# pll_schematic.net
KiCad netlist of a schematic drawn in Altium Designer
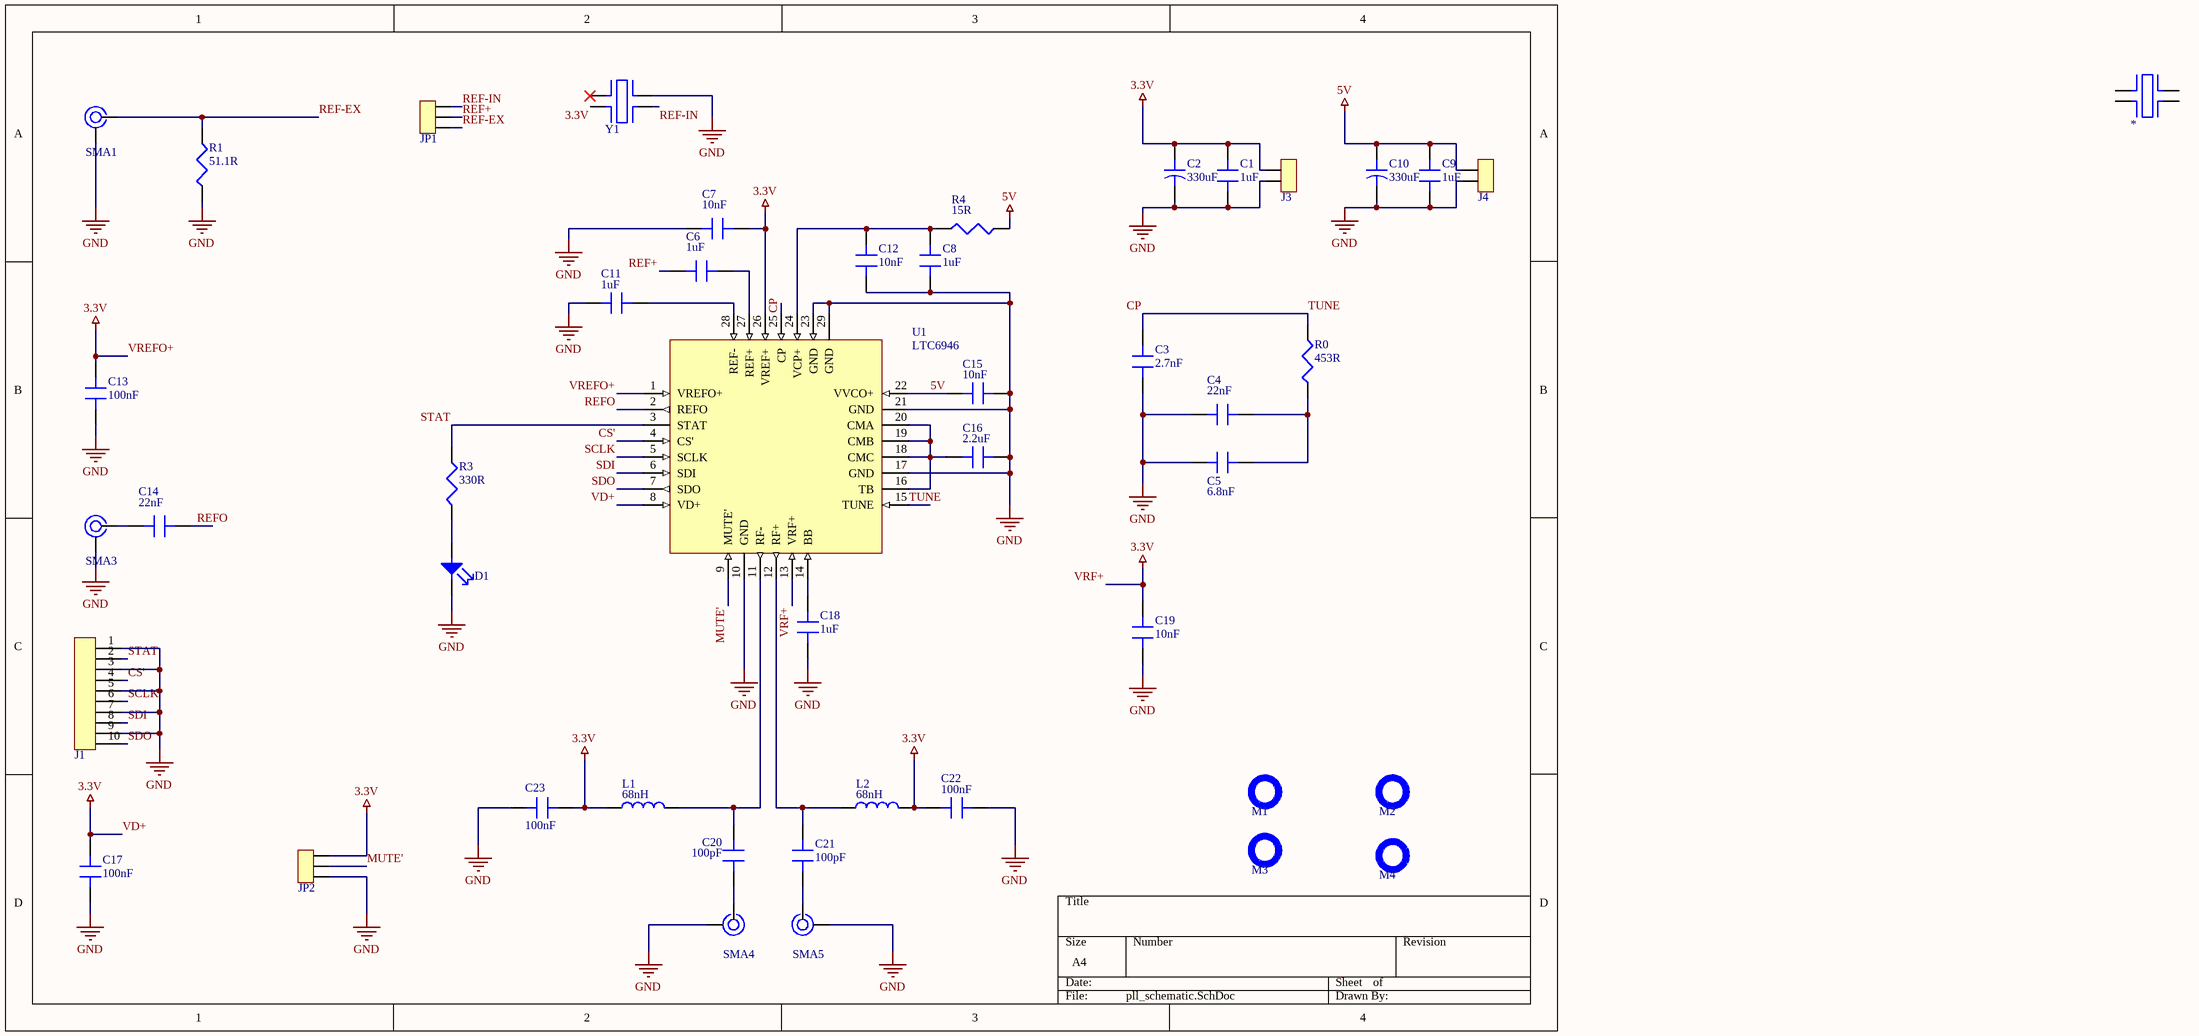
[diagram p0: pll_schematic.SchDoc]

(export (version "E")
  (design (tool "Eeschema 10.0.6"))
  (components
    (comp (ref "*") (value "-") (libsource (lib "pll_schematic_lib") (part "OSC")))
    (comp (ref "C1") (value "1uF") (footprint "C0603") (libsource (lib "pll_schematic_lib") (part "C")))
    (comp (ref "C2") (value "330uF") (footprint "C_TANT_D") (libsource (lib "pll_schematic_lib") (part "CP")))
    (comp (ref "C3") (value "2.7nF") (footprint "C0603") (libsource (lib "pll_schematic_lib") (part "C")))
    (comp (ref "C4") (value "22nF") (footprint "C0603") (libsource (lib "pll_schematic_lib") (part "C")))
    (comp (ref "C5") (value "6.8nF") (footprint "C0603") (libsource (lib "pll_schematic_lib") (part "C")))
    (comp (ref "C6") (value "1uF") (footprint "C0603") (libsource (lib "pll_schematic_lib") (part "C")))
    (comp (ref "C7") (value "10nF") (footprint "C0603") (libsource (lib "pll_schematic_lib") (part "C")))
    (comp (ref "C8") (value "1uF") (footprint "C0603") (libsource (lib "pll_schematic_lib") (part "C")))
    (comp (ref "C9") (value "1uF") (footprint "C0603") (libsource (lib "pll_schematic_lib") (part "C")))
    (comp (ref "C10")
      (value "330uF")
      (footprint "C_TANT_D")
      (libsource (lib "pll_schematic_lib") (part "CP"))
    )
    (comp (ref "C11") (value "1uF") (footprint "C0603") (libsource (lib "pll_schematic_lib") (part "C")))
    (comp (ref "C12") (value "10nF") (footprint "C0603") (libsource (lib "pll_schematic_lib") (part "C")))
    (comp (ref "C13") (value "100nF") (footprint "C0603") (libsource (lib "pll_schematic_lib") (part "C")))
    (comp (ref "C14") (value "22nF") (footprint "C0603") (libsource (lib "pll_schematic_lib") (part "C")))
    (comp (ref "C15") (value "10nF") (footprint "C0603") (libsource (lib "pll_schematic_lib") (part "C")))
    (comp (ref "C16") (value "2.2uF") (footprint "C0805") (libsource (lib "pll_schematic_lib") (part "C")))
    (comp (ref "C17") (value "100nF") (footprint "C0603") (libsource (lib "pll_schematic_lib") (part "C")))
    (comp (ref "C18") (value "1uF") (footprint "C0603") (libsource (lib "pll_schematic_lib") (part "C")))
    (comp (ref "C19") (value "10nF") (footprint "C0603") (libsource (lib "pll_schematic_lib") (part "C")))
    (comp (ref "C20") (value "100pF") (footprint "C0603") (libsource (lib "pll_schematic_lib") (part "C")))
    (comp (ref "C21") (value "100pF") (footprint "C0603") (libsource (lib "pll_schematic_lib") (part "C")))
    (comp (ref "C22") (value "100nF") (footprint "C0603") (libsource (lib "pll_schematic_lib") (part "C")))
    (comp (ref "C23") (value "100nF") (footprint "C0603") (libsource (lib "pll_schematic_lib") (part "C")))
    (comp (ref "D1") (value "-") (footprint "D0805") (libsource (lib "pll_schematic_lib") (part "LED")))
    (comp (ref "J1")
      (value "-")
      (footprint "IDC-2x05")
      (libsource (lib "pll_schematic_lib") (part "Conn_Gene_1x10"))
    )
    (comp (ref "J3")
      (value "-")
      (footprint "DG130-5.0")
      (libsource (lib "pll_schematic_lib") (part "Conn_Gene_1x02"))
    )
    (comp (ref "J4")
      (value "-")
      (footprint "DG130-5.0")
      (libsource (lib "pll_schematic_lib") (part "Conn_Gene_1x02"))
    )
    (comp (ref "JP1")
      (value "-")
      (footprint "PIN_HEADER_1x03")
      (libsource (lib "pll_schematic_lib") (part "Pin Header 1x03"))
    )
    (comp (ref "JP2")
      (value "-")
      (footprint "PIN_HEADER_1x03")
      (libsource (lib "pll_schematic_lib") (part "Pin Header 1x03"))
    )
    (comp (ref "L1") (value "68nH") (footprint "L0402") (libsource (lib "pll_schematic_lib") (part "L")))
    (comp (ref "L2") (value "68nH") (footprint "L0402") (libsource (lib "pll_schematic_lib") (part "L")))
    (comp (ref "M1")
      (value "MOUNTING_HOLE")
      (footprint "MOUNTING_HOLE_NP_M3")
      (description "Non-Plated")
      (libsource (lib "pll_schematic_lib") (part "MOUNTING_HOLE"))
    )
    (comp (ref "M2")
      (value "MOUNTING_HOLE")
      (footprint "MOUNTING_HOLE_NP_M3")
      (description "Non-Plated")
      (libsource (lib "pll_schematic_lib") (part "MOUNTING_HOLE"))
    )
    (comp (ref "M3")
      (value "MOUNTING_HOLE")
      (footprint "MOUNTING_HOLE_NP_M3")
      (description "Non-Plated")
      (libsource (lib "pll_schematic_lib") (part "MOUNTING_HOLE"))
    )
    (comp (ref "M4")
      (value "MOUNTING_HOLE")
      (footprint "MOUNTING_HOLE_NP_M3")
      (description "Non-Plated")
      (libsource (lib "pll_schematic_lib") (part "MOUNTING_HOLE"))
    )
    (comp (ref "R0") (value "453R") (footprint "R0603") (libsource (lib "pll_schematic_lib") (part "R")))
    (comp (ref "R1") (value "51.1R") (footprint "R0603") (libsource (lib "pll_schematic_lib") (part "R")))
    (comp (ref "R3") (value "330R") (footprint "R0603") (libsource (lib "pll_schematic_lib") (part "R")))
    (comp (ref "R4") (value "15R") (footprint "R0603") (libsource (lib "pll_schematic_lib") (part "R")))
    (comp (ref "SMA1") (value "-") (footprint "SMA") (libsource (lib "pll_schematic_lib") (part "SMA")))
    (comp (ref "SMA3") (value "-") (footprint "SMA") (libsource (lib "pll_schematic_lib") (part "SMA")))
    (comp (ref "SMA4") (value "-") (footprint "SMA") (libsource (lib "") (part "SMA_1")))
    (comp (ref "SMA5") (value "-") (footprint "SMA") (libsource (lib "pll_schematic_lib") (part "SMA")))
    (comp (ref "U1")
      (value "LTC6946")
      (footprint "QFN50P400X500X80_HS-29N_2")
      (libsource (lib "pll_schematic_lib") (part "LTC6946IUFD-1#PBF-ND"))
    )
    (comp (ref "Y1") (value "-") (footprint "XOSC") (libsource (lib "pll_schematic_lib") (part "OSC")))
  )
  (nets
    (net (code "1") (name "/CP") (class "Default")
      (node (ref "C3") (pin "2") (pinfunction "-_2") (pintype "passive"))
      (node (ref "R0") (pin "2") (pinfunction "-_2") (pintype "passive"))
      (node (ref "U1") (pin "15") (pinfunction "TUNE_15") (pintype "input"))
      (node (ref "U1") (pin "25") (pinfunction "CP_25") (pintype "input"))
    )
    (net (code "2") (name "/CS'") (class "Default")
      (node (ref "J1") (pin "4") (pinfunction "*_4") (pintype "passive"))
      (node (ref "U1") (pin "4") (pinfunction "CS'_4") (pintype "input"))
    )
    (net (code "3") (name "/MUTE'") (class "Default")
      (node (ref "JP2") (pin "2") (pinfunction "-_2") (pintype "passive"))
      (node (ref "U1") (pin "9") (pinfunction "MUTE'_9") (pintype "input"))
    )
    (net (code "4") (name "/REF+") (class "Default")
      (node (ref "C6") (pin "1") (pinfunction "-_1") (pintype "passive"))
      (node (ref "JP1") (pin "2") (pinfunction "-_2") (pintype "passive"))
    )
    (net (code "5") (name "/REF-EX") (class "Default")
      (node (ref "JP1") (pin "3") (pinfunction "-_3") (pintype "passive"))
      (node (ref "R1") (pin "2") (pinfunction "-_2") (pintype "passive"))
      (node (ref "SMA1") (pin "1") (pinfunction "-_1") (pintype "passive"))
    )
    (net (code "6") (name "/REF-IN") (class "Default")
      (node (ref "JP1") (pin "1") (pinfunction "-_1") (pintype "passive"))
      (node (ref "Y1") (pin "5") (pinfunction "5_5") (pintype "passive"))
    )
    (net (code "7") (name "/REFO") (class "Default")
      (node (ref "C14") (pin "2") (pinfunction "-_2") (pintype "passive"))
      (node (ref "U1") (pin "2") (pinfunction "REFO_2") (pintype "output"))
    )
    (net (code "8") (name "/SCLK") (class "Default")
      (node (ref "J1") (pin "6") (pinfunction "*_6") (pintype "passive"))
      (node (ref "U1") (pin "5") (pinfunction "SCLK_5") (pintype "input"))
    )
    (net (code "9") (name "/SDI") (class "Default")
      (node (ref "J1") (pin "8") (pinfunction "*_8") (pintype "passive"))
      (node (ref "U1") (pin "6") (pinfunction "SDI_6") (pintype "input"))
    )
    (net (code "10") (name "/SDO") (class "Default")
      (node (ref "J1") (pin "10") (pinfunction "*_10") (pintype "passive"))
      (node (ref "U1") (pin "7") (pinfunction "SDO_7") (pintype "output"))
    )
    (net (code "11") (name "/STAT") (class "Default")
      (node (ref "J1") (pin "2") (pinfunction "*_2") (pintype "passive"))
      (node (ref "R3") (pin "2") (pinfunction "-_2") (pintype "passive"))
      (node (ref "U1") (pin "3") (pinfunction "STAT_3") (pintype "passive"))
    )
    (net (code "12") (name "3.3V") (class "Default")
      (node (ref "C1") (pin "2") (pinfunction "-_2") (pintype "passive"))
      (node (ref "C13") (pin "2") (pinfunction "-_2") (pintype "passive"))
      (node (ref "C17") (pin "2") (pinfunction "-_2") (pintype "passive"))
      (node (ref "C19") (pin "2") (pinfunction "-_2") (pintype "passive"))
      (node (ref "C2") (pin "1") (pinfunction "-_1") (pintype "passive"))
      (node (ref "C22") (pin "1") (pinfunction "-_1") (pintype "passive"))
      (node (ref "C23") (pin "1") (pinfunction "-_1") (pintype "passive"))
      (node (ref "C7") (pin "1") (pinfunction "-_1") (pintype "passive"))
      (node (ref "J3") (pin "1") (pinfunction "-_1") (pintype "passive"))
      (node (ref "JP2") (pin "1") (pinfunction "-_1") (pintype "passive"))
      (node (ref "L1") (pin "1") (pinfunction "-_1") (pintype "passive"))
      (node (ref "L2") (pin "2") (pinfunction "-_2") (pintype "passive"))
      (node (ref "U1") (pin "1") (pinfunction "VREFO+_1") (pintype "input"))
      (node (ref "U1") (pin "13") (pinfunction "VRF+_13") (pintype "input"))
      (node (ref "U1") (pin "26") (pinfunction "VREF+_26") (pintype "input"))
      (node (ref "U1") (pin "8") (pinfunction "VD+_8") (pintype "input"))
      (node (ref "Y1") (pin "8") (pinfunction "8_8") (pintype "passive"))
    )
    (net (code "13") (name "5V") (class "Default")
      (node (ref "C10") (pin "1") (pinfunction "-_1") (pintype "passive"))
      (node (ref "C15") (pin "1") (pinfunction "-_1") (pintype "passive"))
      (node (ref "C9") (pin "1") (pinfunction "-_1") (pintype "passive"))
      (node (ref "J4") (pin "1") (pinfunction "-_1") (pintype "passive"))
      (node (ref "R4") (pin "2") (pinfunction "-_2") (pintype "passive"))
      (node (ref "U1") (pin "22") (pinfunction "VVCO+_22") (pintype "input"))
    )
    (net (code "14") (name "GND") (class "Default")
      (node (ref "C1") (pin "1") (pinfunction "-_1") (pintype "passive"))
      (node (ref "C10") (pin "2") (pinfunction "-_2") (pintype "passive"))
      (node (ref "C11") (pin "1") (pinfunction "-_1") (pintype "passive"))
      (node (ref "C12") (pin "2") (pinfunction "-_2") (pintype "passive"))
      (node (ref "C13") (pin "1") (pinfunction "-_1") (pintype "passive"))
      (node (ref "C15") (pin "2") (pinfunction "-_2") (pintype "passive"))
      (node (ref "C16") (pin "2") (pinfunction "-_2") (pintype "passive"))
      (node (ref "C17") (pin "1") (pinfunction "-_1") (pintype "passive"))
      (node (ref "C18") (pin "1") (pinfunction "-_1") (pintype "passive"))
      (node (ref "C19") (pin "1") (pinfunction "-_1") (pintype "passive"))
      (node (ref "C2") (pin "2") (pinfunction "-_2") (pintype "passive"))
      (node (ref "C22") (pin "2") (pinfunction "-_2") (pintype "passive"))
      (node (ref "C23") (pin "2") (pinfunction "-_2") (pintype "passive"))
      (node (ref "C3") (pin "1") (pinfunction "-_1") (pintype "passive"))
      (node (ref "C4") (pin "2") (pinfunction "-_2") (pintype "passive"))
      (node (ref "C5") (pin "2") (pinfunction "-_2") (pintype "passive"))
      (node (ref "C7") (pin "2") (pinfunction "-_2") (pintype "passive"))
      (node (ref "C8") (pin "1") (pinfunction "-_1") (pintype "passive"))
      (node (ref "C9") (pin "2") (pinfunction "-_2") (pintype "passive"))
      (node (ref "D1") (pin "C") (pinfunction "C_C") (pintype "passive"))
      (node (ref "J1") (pin "1") (pinfunction "*_1") (pintype "passive"))
      (node (ref "J1") (pin "3") (pinfunction "*_3") (pintype "passive"))
      (node (ref "J1") (pin "5") (pinfunction "*_5") (pintype "passive"))
      (node (ref "J1") (pin "7") (pinfunction "*_7") (pintype "passive"))
      (node (ref "J1") (pin "9") (pinfunction "*_9") (pintype "passive"))
      (node (ref "J3") (pin "2") (pinfunction "-_2") (pintype "passive"))
      (node (ref "J4") (pin "2") (pinfunction "-_2") (pintype "passive"))
      (node (ref "JP2") (pin "3") (pinfunction "-_3") (pintype "passive"))
      (node (ref "R1") (pin "1") (pinfunction "-_1") (pintype "passive"))
      (node (ref "SMA1") (pin "2") (pinfunction "-_2") (pintype "passive"))
      (node (ref "SMA3") (pin "2") (pinfunction "-_2") (pintype "passive"))
      (node (ref "SMA4") (pin "2") (pinfunction "-_2") (pintype "passive"))
      (node (ref "SMA5") (pin "2") (pinfunction "-_2") (pintype "passive"))
      (node (ref "U1") (pin "10") (pinfunction "GND_10") (pintype "passive"))
      (node (ref "U1") (pin "17") (pinfunction "GND_17") (pintype "passive"))
      (node (ref "U1") (pin "21") (pinfunction "GND_21") (pintype "passive"))
      (node (ref "U1") (pin "23") (pinfunction "GND_23") (pintype "input"))
      (node (ref "U1") (pin "29") (pinfunction "GND_29") (pintype "passive"))
      (node (ref "Y1") (pin "4") (pinfunction "4_4") (pintype "passive"))
    )
    (net (code "15") (name "Net-(C4---Pad1)") (class "Default")
      (node (ref "C4") (pin "1") (pinfunction "-_1") (pintype "passive"))
      (node (ref "C5") (pin "1") (pinfunction "-_1") (pintype "passive"))
      (node (ref "R0") (pin "1") (pinfunction "-_1") (pintype "passive"))
    )
    (net (code "16") (name "Net-(C14---Pad1)") (class "Default")
      (node (ref "C14") (pin "1") (pinfunction "-_1") (pintype "passive"))
      (node (ref "SMA3") (pin "1") (pinfunction "-_1") (pintype "passive"))
    )
    (net (code "17") (name "Net-(C20---Pad1)") (class "Default")
      (node (ref "C20") (pin "1") (pinfunction "-_1") (pintype "passive"))
      (node (ref "SMA4") (pin "1") (pinfunction "-_1") (pintype "passive"))
    )
    (net (code "18") (name "Net-(C21---Pad1)") (class "Default")
      (node (ref "C21") (pin "1") (pinfunction "-_1") (pintype "passive"))
      (node (ref "SMA5") (pin "1") (pinfunction "-_1") (pintype "passive"))
    )
    (net (code "19") (name "Net-(D1-PadA)") (class "Default")
      (node (ref "D1") (pin "A") (pinfunction "A_A") (pintype "passive"))
      (node (ref "R3") (pin "1") (pinfunction "-_1") (pintype "passive"))
    )
    (net (code "20") (name "Net-(U1-BB)") (class "Default")
      (node (ref "C18") (pin "2") (pinfunction "-_2") (pintype "passive"))
      (node (ref "U1") (pin "14") (pinfunction "BB_14") (pintype "input"))
    )
    (net (code "21") (name "Net-(U1-CMA)") (class "Default")
      (node (ref "C16") (pin "1") (pinfunction "-_1") (pintype "passive"))
      (node (ref "U1") (pin "16") (pinfunction "TB_16") (pintype "passive"))
      (node (ref "U1") (pin "18") (pinfunction "CMC_18") (pintype "passive"))
      (node (ref "U1") (pin "19") (pinfunction "CMB_19") (pintype "passive"))
      (node (ref "U1") (pin "20") (pinfunction "CMA_20") (pintype "passive"))
    )
    (net (code "22") (name "Net-(U1-REF+)") (class "Default")
      (node (ref "C6") (pin "2") (pinfunction "-_2") (pintype "passive"))
      (node (ref "U1") (pin "27") (pinfunction "REF+_27") (pintype "input"))
    )
    (net (code "23") (name "Net-(U1-REF-)") (class "Default")
      (node (ref "C11") (pin "2") (pinfunction "-_2") (pintype "passive"))
      (node (ref "U1") (pin "28") (pinfunction "REF-_28") (pintype "input"))
    )
    (net (code "24") (name "Net-(U1-RF+)") (class "Default")
      (node (ref "C21") (pin "2") (pinfunction "-_2") (pintype "passive"))
      (node (ref "L2") (pin "1") (pinfunction "-_1") (pintype "passive"))
      (node (ref "U1") (pin "12") (pinfunction "RF+_12") (pintype "output"))
    )
    (net (code "25") (name "Net-(U1-RF-)") (class "Default")
      (node (ref "C20") (pin "2") (pinfunction "-_2") (pintype "passive"))
      (node (ref "L1") (pin "2") (pinfunction "-_2") (pintype "passive"))
      (node (ref "U1") (pin "11") (pinfunction "RF-_11") (pintype "output"))
    )
    (net (code "26") (name "Net-(U1-VCP+)") (class "Default")
      (node (ref "C12") (pin "1") (pinfunction "-_1") (pintype "passive"))
      (node (ref "C8") (pin "2") (pinfunction "-_2") (pintype "passive"))
      (node (ref "R4") (pin "1") (pinfunction "-_1") (pintype "passive"))
      (node (ref "U1") (pin "24") (pinfunction "VCP+_24") (pintype "input"))
    )
    (net (code "27") (name "unconnected-(*-Pad1)") (class "Default")
      (node (ref "*") (pin "1") (pinfunction "1_1") (pintype "passive"))
    )
    (net (code "28") (name "unconnected-(*-Pad4)") (class "Default")
      (node (ref "*") (pin "4") (pinfunction "4_4") (pintype "passive"))
    )
    (net (code "29") (name "unconnected-(*-Pad5)") (class "Default")
      (node (ref "*") (pin "5") (pinfunction "5_5") (pintype "passive"))
    )
    (net (code "30") (name "unconnected-(*-Pad8)") (class "Default")
      (node (ref "*") (pin "8") (pinfunction "8_8") (pintype "passive"))
    )
    (net (code "31") (name "unconnected-(Y1-Pad1)") (class "Default")
      (node (ref "Y1") (pin "1") (pinfunction "1_1") (pintype "passive+no_connect"))
    )
  )
)
